# Main.net
KiCad netlist of a schematic drawn in Altium Designer
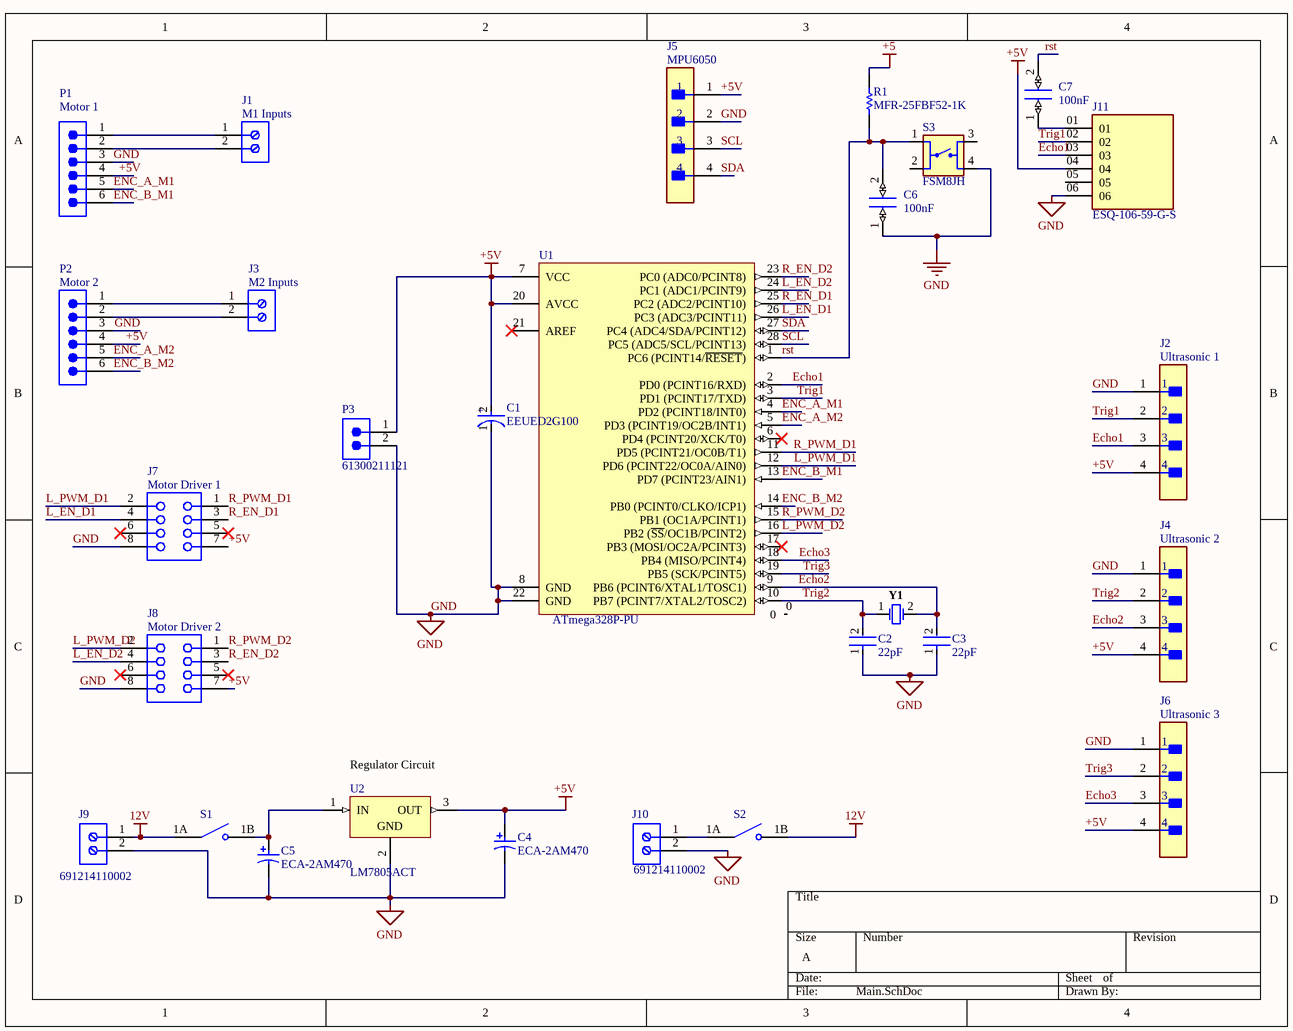
[diagram p0: Main.SchDoc]

(export (version "E")
  (design (tool "Eeschema 10.0.6"))
  (components
    (comp (ref "C1")
      (value "EEUED2G100")
      (footprint "FP-RAD-TH-D_10_0_5-L_20_2-MFG")
      (description "Aluminum Electrolytic Capacitors (Radial Lead Type) 10uF ±20% 400V")
      (fields (field (name "VOLTAGE") "400V") (field (name "TOLERANCE") "20%"))
      (libsource (lib "Altium Content Vault") (part "203bc49f2ac43e59fd269a8c329ed05"))
    )
    (comp (ref "C2")
      (value "RDE5C2A220J0M1H03A")
      (footprint "FP-RDE0M1-MFG")
      (description "Ceramic Capacitor 22pF ±5% 100V C0G Radial")
      (fields (field (name "CAPACITANCE") "22pF") (field (name "TOLERANCE") "5%"))
      (libsource (lib "Altium Content Vault") (part "b4654b650e69147ec39a6b967a45e02"))
    )
    (comp (ref "C3")
      (value "RDE5C2A220J0M1H03A")
      (footprint "FP-RDE0M1-MFG")
      (description "Ceramic Capacitor 22pF ±5% 100V C0G Radial")
      (fields (field (name "CAPACITANCE") "22pF") (field (name "TOLERANCE") "5%"))
      (libsource (lib "Altium Content Vault") (part "b4654b650e69147ec39a6b967a45e02"))
    )
    (comp (ref "C4")
      (value "ECA-2AM470")
      (footprint "CAPPR65-350-1150X800X1250")
      (description "Aluminum Electrolytic Capacitor, 47 uF, +/- 20%, 100 V, -40 to 85 degC, 2-Pin THD, RoHS, Bulk")
      (libsource (lib "Altium Content Vault") (part "CAP-P-2"))
    )
    (comp (ref "C5")
      (value "ECA-2AM470")
      (footprint "CAPPR65-350-1150X800X1250")
      (description "Aluminum Electrolytic Capacitor, 47 uF, +/- 20%, 100 V, -40 to 85 degC, 2-Pin THD, RoHS, Bulk")
      (libsource (lib "Altium Content Vault") (part "CAP-P-2"))
    )
    (comp (ref "C6")
      (value "100nF")
      (footprint "C320C")
      (description "0.1ÂµF Â±20% 50V Ceramic Capacitor Z5U Radial")
      (fields (field (name "MF") "KEMET") (field (name "MP") "C320C104M5U5TA"))
      (libsource (lib "C320C104M5U5TA") (part "C320C104M5U5TA"))
    )
    (comp (ref "C7")
      (value "100nF")
      (footprint "C320C")
      (description "0.1ÂµF Â±20% 50V Ceramic Capacitor Z5U Radial")
      (fields (field (name "MF") "KEMET") (field (name "MP") "C320C104M5U5TA"))
      (libsource (lib "C320C104M5U5TA") (part "C320C104M5U5TA"))
    )
    (comp (ref "J1")
      (value "691214110002")
      (footprint "691214110002")
      (fields (field (name "VOLTAGE") "300V"))
      (libsource (lib "Altium Content Vault") (part "TBL - 1R - 02P - Screw"))
    )
    (comp (ref "J2")
      (value "Ultrasonic 1")
      (footprint "FP-B4B-XH-A_LF_SN-MFG")
      (description "CONN HEADER VERT 4POS 2.5MM")
      (libsource (lib "Altium Content Vault") (part "299a8cea1bdcbc3624fe62c390fa72c"))
    )
    (comp (ref "J3")
      (value "691214110002")
      (footprint "691214110002")
      (fields (field (name "VOLTAGE") "300V"))
      (libsource (lib "Altium Content Vault") (part "TBL - 1R - 02P - Screw"))
    )
    (comp (ref "J4")
      (value "Ultrasonic 2")
      (footprint "FP-B4B-XH-A_LF_SN-MFG")
      (description "CONN HEADER VERT 4POS 2.5MM")
      (libsource (lib "Altium Content Vault") (part "299a8cea1bdcbc3624fe62c390fa72c"))
    )
    (comp (ref "J5")
      (value "MPU6050")
      (footprint "FP-M20-9990445-MFG")
      (description "M20-9990445 Conn Unshrouded Header HDR 4 POS 2.54mm Solder ST Thru-Hole Bulk/Loose")
      (libsource (lib "") (part "299a8cea1bdcbc3624fe62c390fa72c_1"))
    )
    (comp (ref "J6")
      (value "Ultrasonic 3")
      (footprint "FP-B4B-XH-A_LF_SN-MFG")
      (description "CONN HEADER VERT 4POS 2.5MM")
      (libsource (lib "Altium Content Vault") (part "299a8cea1bdcbc3624fe62c390fa72c"))
    )
    (comp (ref "J7")
      (value "Motor Driver 1")
      (footprint "SMTC-SSW-104-02-X-D")
      (description "SQ Post Socket, Through-hole, Vertical, -55 to 125 degC, 2.54mm Pitch, 8-Pin, Female, RoHS")
      (fields (field (name "MANUFACTURER") "Samtec") (field (name "PARTNUMBER") "SSW-104-02-G-D"))
      (libsource (lib "Altium Content Vault") (part "SMTC-SSW-104-X-X-D"))
    )
    (comp (ref "J8")
      (value "Motor Driver 2")
      (footprint "SMTC-SSW-104-02-X-D")
      (description "SQ Post Socket, Through-hole, Vertical, -55 to 125 degC, 2.54mm Pitch, 8-Pin, Female, RoHS")
      (fields (field (name "MANUFACTURER") "Samtec") (field (name "PARTNUMBER") "SSW-104-02-G-D"))
      (libsource (lib "Altium Content Vault") (part "SMTC-SSW-104-X-X-D"))
    )
    (comp (ref "J9")
      (value "691214110002")
      (footprint "691214110002")
      (fields (field (name "VOLTAGE") "300V"))
      (libsource (lib "Altium Content Vault") (part "TBL - 1R - 02P - Screw"))
    )
    (comp (ref "J10")
      (value "691214110002")
      (footprint "691214110002")
      (fields (field (name "VOLTAGE") "300V"))
      (libsource (lib "Altium Content Vault") (part "TBL - 1R - 02P - Screw"))
    )
    (comp (ref "J11")
      (value "ESQ-106-59-G-S")
      (footprint "SAMTEC_ESQ-106-59-G-S")
      (libsource (lib "ESQ-106-59-G-S") (part "ESQ-106-59-G-S"))
    )
    (comp (ref "P1")
      (value "Motor 1")
      (footprint "61300611121")
      (libsource (lib "Altium Content Vault") (part "Header_Male_1R_06P"))
    )
    (comp (ref "P2")
      (value "Motor 2")
      (footprint "61300611121")
      (libsource (lib "Altium Content Vault") (part "Header_Male_1R_06P"))
    )
    (comp (ref "P3")
      (value "61300211121")
      (footprint "61300211121")
      (libsource (lib "Altium Content Vault") (part "Header_Male_1R_02P"))
    )
    (comp (ref "R1")
      (value "MFR-25FBF52-1K")
      (footprint "RESA60-630X240")
      (description "Axial Resistor, 1 KOhm, +/- 1%, 250 mW, -55 to 155 degC, 2-Pin THD, RoHS, Bulk")
      (fields (field (name "TOLERANCE") "1%"))
      (libsource (lib "Altium Content Vault") (part "RES-2"))
    )
    (comp (ref "S1")
      (value "DS01-254-L-01BE")
      (footprint "SW_DS01-254-L-01BE")
      (description "1 Position, Through Hole, 2.54 mm Pitch, Raised Slide Actuator, Flat Bottom, Long Pin, DIP Switch")
      (fields (field (name "MF") "CUI Devices"))
      (libsource (lib "DS01-254-L-01BE") (part "DS01-254-L-01BE"))
    )
    (comp (ref "S2")
      (value "DS01-254-L-01BE")
      (footprint "SW_DS01-254-L-01BE")
      (description "1 Position, Through Hole, 2.54 mm Pitch, Raised Slide Actuator, Flat Bottom, Long Pin, DIP Switch")
      (fields (field (name "MF") "CUI Devices"))
      (libsource (lib "DS01-254-L-01BE") (part "DS01-254-L-01BE"))
    )
    (comp (ref "S3")
      (value "FSM8JH")
      (footprint "SW_FSM8JH")
      (description "Tactile Switch SPST-NO Top Actuated Through Hole")
      (fields (field (name "MF") "TE Connectivity"))
      (libsource (lib "FSM8JH") (part "FSM8JH"))
    )
    (comp (ref "U1")
      (value "ATmega328P-PU")
      (footprint "28P3")
      (libsource (lib "Altium Content Vault") (part "MC-8B-ATM48-IL28"))
    )
    (comp (ref "U2")
      (value "LM7805ACT")
      (footprint "FAIR-TO-220-3")
      (description "Positive Voltage Regulator, 5 V, 1 A, 0 to 125 degC, 3-Pin TO-220, RoHS, Tube")
      (fields (field (name "MANUFACTURER") "Fairchild"))
      (libsource (lib "Altium Content Vault") (part "FAIR-LM7805CT-TO220-3"))
    )
    (comp (ref "Y1")
      (value "FOXSLF/160-20")
      (footprint "FOX-FOXSLF160-20")
      (description "Resistance Weld Thru-Hole Crystal, 16 MHz, -20 to 70 degC, 2-Pin THD, RoHS, Bulk")
      (fields (field (name "TOLERANCE") "1%"))
      (libsource (lib "Altium Content Vault") (part "XTAL-1-2-2"))
    )
  )
  (nets
    (net (code "1") (name "+5") (class "Default")
      (node (ref "R1") (pin "1") (pinfunction "1_1") (pintype "passive"))
    )
    (net (code "2") (name "+5V") (class "Default")
      (node (ref "C1") (pin "2") (pinfunction "A_2") (pintype "passive"))
      (node (ref "C4") (pin "1") (pinfunction "1_1") (pintype "passive"))
      (node (ref "J11") (pin "04") (pinfunction "04_04") (pintype "passive"))
      (node (ref "J2") (pin "4") (pinfunction "4_4") (pintype "passive"))
      (node (ref "J4") (pin "4") (pinfunction "4_4") (pintype "passive"))
      (node (ref "J5") (pin "1") (pinfunction "1_1") (pintype "passive"))
      (node (ref "J6") (pin "4") (pinfunction "4_4") (pintype "passive"))
      (node (ref "J7") (pin "7") (pinfunction "7_7") (pintype "passive"))
      (node (ref "J8") (pin "7") (pinfunction "7_7") (pintype "passive"))
      (node (ref "P1") (pin "4") (pinfunction "4_4") (pintype "passive"))
      (node (ref "P2") (pin "4") (pinfunction "4_4") (pintype "passive"))
      (node (ref "P3") (pin "1") (pinfunction "1_1") (pintype "passive"))
      (node (ref "U1") (pin "20") (pinfunction "AVCC_20") (pintype "power_in"))
      (node (ref "U1") (pin "7") (pinfunction "VCC_7") (pintype "power_in"))
      (node (ref "U2") (pin "3") (pinfunction "OUT_3") (pintype "output"))
    )
    (net (code "3") (name "/ENC_A_M1") (class "Default")
      (node (ref "P1") (pin "5") (pinfunction "5_5") (pintype "passive"))
      (node (ref "U1") (pin "4") (pinfunction "PD2_(PCINT18/INT0)_4") (pintype "input"))
    )
    (net (code "4") (name "/ENC_A_M2") (class "Default")
      (node (ref "P2") (pin "5") (pinfunction "5_5") (pintype "passive"))
      (node (ref "U1") (pin "5") (pinfunction "PD3_(PCINT19/OC2B/INT1)_5") (pintype "input"))
    )
    (net (code "5") (name "/ENC_B_M1") (class "Default")
      (node (ref "P1") (pin "6") (pinfunction "6_6") (pintype "passive"))
      (node (ref "U1") (pin "13") (pinfunction "PD7_(PCINT23/AIN1)_13") (pintype "input"))
    )
    (net (code "6") (name "/ENC_B_M2") (class "Default")
      (node (ref "P2") (pin "6") (pinfunction "6_6") (pintype "passive"))
      (node (ref "U1") (pin "14") (pinfunction "PB0_(PCINT0/CLKO/ICP1)_14") (pintype "input"))
    )
    (net (code "7") (name "/Echo1") (class "Default")
      (node (ref "J11") (pin "03") (pinfunction "03_03") (pintype "passive"))
      (node (ref "J2") (pin "3") (pinfunction "3_3") (pintype "passive"))
      (node (ref "U1") (pin "2") (pinfunction "PD0_(PCINT16/RXD)_2") (pintype "bidirectional"))
    )
    (net (code "8") (name "/Echo2") (class "Default")
      (node (ref "C3") (pin "2") (pinfunction "2_2") (pintype "passive"))
      (node (ref "J4") (pin "3") (pinfunction "3_3") (pintype "passive"))
      (node (ref "U1") (pin "9") (pinfunction "PB6_(PCINT6/XTAL1/TOSC1)_9") (pintype "bidirectional"))
      (node (ref "Y1") (pin "2") (pinfunction "2_2") (pintype "passive"))
    )
    (net (code "9") (name "/Echo3") (class "Default")
      (node (ref "J6") (pin "3") (pinfunction "3_3") (pintype "passive"))
      (node (ref "U1") (pin "18") (pinfunction "PB4_(MISO/PCINT4)_18") (pintype "bidirectional"))
    )
    (net (code "10") (name "/L_EN_D1") (class "Default")
      (node (ref "J7") (pin "4") (pinfunction "4_4") (pintype "passive"))
      (node (ref "U1") (pin "26") (pinfunction "PC3_(ADC3/PCINT11)_26") (pintype "output"))
    )
    (net (code "11") (name "/L_EN_D2") (class "Default")
      (node (ref "J8") (pin "4") (pinfunction "4_4") (pintype "passive"))
      (node (ref "U1") (pin "24") (pinfunction "PC1_(ADC1/PCINT9)_24") (pintype "output"))
    )
    (net (code "12") (name "/L_PWM_D1") (class "Default")
      (node (ref "J7") (pin "2") (pinfunction "2_2") (pintype "passive"))
      (node (ref "U1") (pin "12") (pinfunction "PD6_(PCINT22/OC0A/AIN0)_12") (pintype "output"))
    )
    (net (code "13") (name "/L_PWM_D2") (class "Default")
      (node (ref "J8") (pin "2") (pinfunction "2_2") (pintype "passive"))
      (node (ref "U1") (pin "16") (pinfunction "PB2_(~{SS}/OC1B/PCINT2)_16") (pintype "output"))
    )
    (net (code "14") (name "/R_EN_D1") (class "Default")
      (node (ref "J7") (pin "3") (pinfunction "3_3") (pintype "passive"))
      (node (ref "U1") (pin "25") (pinfunction "PC2_(ADC2/PCINT10)_25") (pintype "output"))
    )
    (net (code "15") (name "/R_EN_D2") (class "Default")
      (node (ref "J8") (pin "3") (pinfunction "3_3") (pintype "passive"))
      (node (ref "U1") (pin "23") (pinfunction "PC0_(ADC0/PCINT8)_23") (pintype "output"))
    )
    (net (code "16") (name "/R_PWM_D1") (class "Default")
      (node (ref "J7") (pin "1") (pinfunction "1_1") (pintype "passive"))
      (node (ref "U1") (pin "11") (pinfunction "PD5_(PCINT21/OC0B/T1)_11") (pintype "output"))
    )
    (net (code "17") (name "/R_PWM_D2") (class "Default")
      (node (ref "J8") (pin "1") (pinfunction "1_1") (pintype "passive"))
      (node (ref "U1") (pin "15") (pinfunction "PB1_(OC1A/PCINT1)_15") (pintype "output"))
    )
    (net (code "18") (name "/SCL") (class "Default")
      (node (ref "J5") (pin "3") (pinfunction "3_3") (pintype "passive"))
      (node (ref "U1") (pin "28") (pinfunction "PC5_(ADC5/SCL/PCINT13)_28") (pintype "bidirectional"))
    )
    (net (code "19") (name "/SDA") (class "Default")
      (node (ref "J5") (pin "4") (pinfunction "4_4") (pintype "passive"))
      (node (ref "U1") (pin "27") (pinfunction "PC4_(ADC4/SDA/PCINT12)_27") (pintype "bidirectional"))
    )
    (net (code "20") (name "/Trig1") (class "Default")
      (node (ref "J11") (pin "02") (pinfunction "02_02") (pintype "passive"))
      (node (ref "J2") (pin "2") (pinfunction "2_2") (pintype "passive"))
      (node (ref "U1") (pin "3") (pinfunction "PD1_(PCINT17/TXD)_3") (pintype "bidirectional"))
    )
    (net (code "21") (name "/Trig2") (class "Default")
      (node (ref "C2") (pin "2") (pinfunction "2_2") (pintype "passive"))
      (node (ref "J4") (pin "2") (pinfunction "2_2") (pintype "passive"))
      (node (ref "U1") (pin "10") (pinfunction "PB7_(PCINT7/XTAL2/TOSC2)_10") (pintype "bidirectional"))
      (node (ref "Y1") (pin "1") (pinfunction "1_1") (pintype "passive"))
    )
    (net (code "22") (name "/Trig3") (class "Default")
      (node (ref "J6") (pin "2") (pinfunction "2_2") (pintype "passive"))
      (node (ref "U1") (pin "19") (pinfunction "PB5_(SCK/PCINT5)_19") (pintype "bidirectional"))
    )
    (net (code "23") (name "/rst") (class "Default")
      (node (ref "C6") (pin "2") (pinfunction "2_2") (pintype "bidirectional"))
      (node (ref "C7") (pin "2") (pinfunction "2_2") (pintype "bidirectional"))
      (node (ref "R1") (pin "2") (pinfunction "2_2") (pintype "passive"))
      (node (ref "S3") (pin "1") (pinfunction "1_1") (pintype "passive"))
      (node (ref "U1") (pin "1") (pinfunction "PC6_(PCINT14/~{RESET})_1") (pintype "bidirectional"))
    )
    (net (code "24") (name "12V") (class "Default")
      (node (ref "J9") (pin "1") (pinfunction "1_1") (pintype "passive"))
      (node (ref "S1") (pin "1A") (pinfunction "COM1_1A") (pintype "passive"))
      (node (ref "S2") (pin "1B") (pinfunction "NO1_1B") (pintype "passive"))
    )
    (net (code "25") (name "GND") (class "Default")
      (node (ref "C1") (pin "1") (pinfunction "C_1") (pintype "passive"))
      (node (ref "C2") (pin "1") (pinfunction "1_1") (pintype "passive"))
      (node (ref "C3") (pin "1") (pinfunction "1_1") (pintype "passive"))
      (node (ref "C4") (pin "2") (pinfunction "2_2") (pintype "passive"))
      (node (ref "C5") (pin "2") (pinfunction "2_2") (pintype "passive"))
      (node (ref "C6") (pin "1") (pinfunction "1_1") (pintype "bidirectional"))
      (node (ref "J10") (pin "2") (pinfunction "2_2") (pintype "passive"))
      (node (ref "J11") (pin "06") (pinfunction "06_06") (pintype "passive"))
      (node (ref "J2") (pin "1") (pinfunction "1_1") (pintype "passive"))
      (node (ref "J4") (pin "1") (pinfunction "1_1") (pintype "passive"))
      (node (ref "J5") (pin "2") (pinfunction "2_2") (pintype "passive"))
      (node (ref "J6") (pin "1") (pinfunction "1_1") (pintype "passive"))
      (node (ref "J7") (pin "8") (pinfunction "8_8") (pintype "passive"))
      (node (ref "J8") (pin "8") (pinfunction "8_8") (pintype "passive"))
      (node (ref "J9") (pin "2") (pinfunction "2_2") (pintype "passive"))
      (node (ref "P1") (pin "3") (pinfunction "3_3") (pintype "passive"))
      (node (ref "P2") (pin "3") (pinfunction "3_3") (pintype "passive"))
      (node (ref "P3") (pin "2") (pinfunction "2_2") (pintype "passive"))
      (node (ref "S3") (pin "4") (pinfunction "4_4") (pintype "passive"))
      (node (ref "U1") (pin "22") (pinfunction "GND_22") (pintype "power_in"))
      (node (ref "U1") (pin "8") (pinfunction "GND_8") (pintype "power_in"))
      (node (ref "U2") (pin "2") (pinfunction "GND_2") (pintype "power_in"))
    )
    (net (code "26") (name "Net-(C7-Pad1)") (class "Default")
      (node (ref "C7") (pin "1") (pinfunction "1_1") (pintype "bidirectional"))
      (node (ref "J11") (pin "01") (pinfunction "01_01") (pintype "passive"))
    )
    (net (code "27") (name "Net-(J1-Pad1)") (class "Default")
      (node (ref "J1") (pin "1") (pinfunction "1_1") (pintype "passive"))
      (node (ref "P1") (pin "1") (pinfunction "1_1") (pintype "passive"))
    )
    (net (code "28") (name "Net-(J1-Pad2)") (class "Default")
      (node (ref "J1") (pin "2") (pinfunction "2_2") (pintype "passive"))
      (node (ref "P1") (pin "2") (pinfunction "2_2") (pintype "passive"))
    )
    (net (code "29") (name "Net-(J3-Pad1)") (class "Default")
      (node (ref "J3") (pin "1") (pinfunction "1_1") (pintype "passive"))
      (node (ref "P2") (pin "1") (pinfunction "1_1") (pintype "passive"))
    )
    (net (code "30") (name "Net-(J3-Pad2)") (class "Default")
      (node (ref "J3") (pin "2") (pinfunction "2_2") (pintype "passive"))
      (node (ref "P2") (pin "2") (pinfunction "2_2") (pintype "passive"))
    )
    (net (code "31") (name "Net-(S1-NO1)") (class "Default")
      (node (ref "C5") (pin "1") (pinfunction "1_1") (pintype "passive"))
      (node (ref "S1") (pin "1B") (pinfunction "NO1_1B") (pintype "passive"))
      (node (ref "U2") (pin "1") (pinfunction "IN_1") (pintype "input"))
    )
    (net (code "32") (name "Net-(S2-COM1)") (class "Default")
      (node (ref "J10") (pin "1") (pinfunction "1_1") (pintype "passive"))
      (node (ref "S2") (pin "1A") (pinfunction "COM1_1A") (pintype "passive"))
    )
    (net (code "33") (name "unconnected-(J7-Pad5)") (class "Default")
      (node (ref "J7") (pin "5") (pinfunction "5_5") (pintype "passive+no_connect"))
    )
    (net (code "34") (name "unconnected-(J7-Pad6)") (class "Default")
      (node (ref "J7") (pin "6") (pinfunction "6_6") (pintype "passive+no_connect"))
    )
    (net (code "35") (name "unconnected-(J8-Pad5)") (class "Default")
      (node (ref "J8") (pin "5") (pinfunction "5_5") (pintype "passive+no_connect"))
    )
    (net (code "36") (name "unconnected-(J8-Pad6)") (class "Default")
      (node (ref "J8") (pin "6") (pinfunction "6_6") (pintype "passive+no_connect"))
    )
    (net (code "37") (name "unconnected-(J11-Pad05)") (class "Default")
      (node (ref "J11") (pin "05") (pinfunction "05_05") (pintype "passive"))
    )
    (net (code "38") (name "unconnected-(S3-Pad2)") (class "Default")
      (node (ref "S3") (pin "2") (pinfunction "2_2") (pintype "passive"))
    )
    (net (code "39") (name "unconnected-(S3-Pad3)") (class "Default")
      (node (ref "S3") (pin "3") (pinfunction "3_3") (pintype "passive"))
    )
    (net (code "40") (name "unconnected-(U1-AREF-Pad21)") (class "Default")
      (node (ref "U1") (pin "21") (pinfunction "AREF_21") (pintype "power_in+no_connect"))
    )
    (net (code "41") (name "unconnected-(U1-PB3_(MOSI{slash}OC2A{slash}PCINT3)-Pad17)") (class "Default")
      (node (ref "U1") (pin "17") (pinfunction "PB3_(MOSI/OC2A/PCINT3)_17") (pintype "bidirectional+no_connect"))
    )
    (net (code "42") (name "unconnected-(U1-PD4_(PCINT20{slash}XCK{slash}T0)-Pad6)") (class "Default")
      (node (ref "U1") (pin "6") (pinfunction "PD4_(PCINT20/XCK/T0)_6") (pintype "bidirectional+no_connect"))
    )
    (net (code "43") (name "unconnected-(U1-Pad0)") (class "Default")
      (node (ref "U1") (pin "0") (pinfunction "0_0") (pintype "passive"))
    )
  )
)
